# Power.net
KiCad netlist of a schematic drawn in Altium Designer
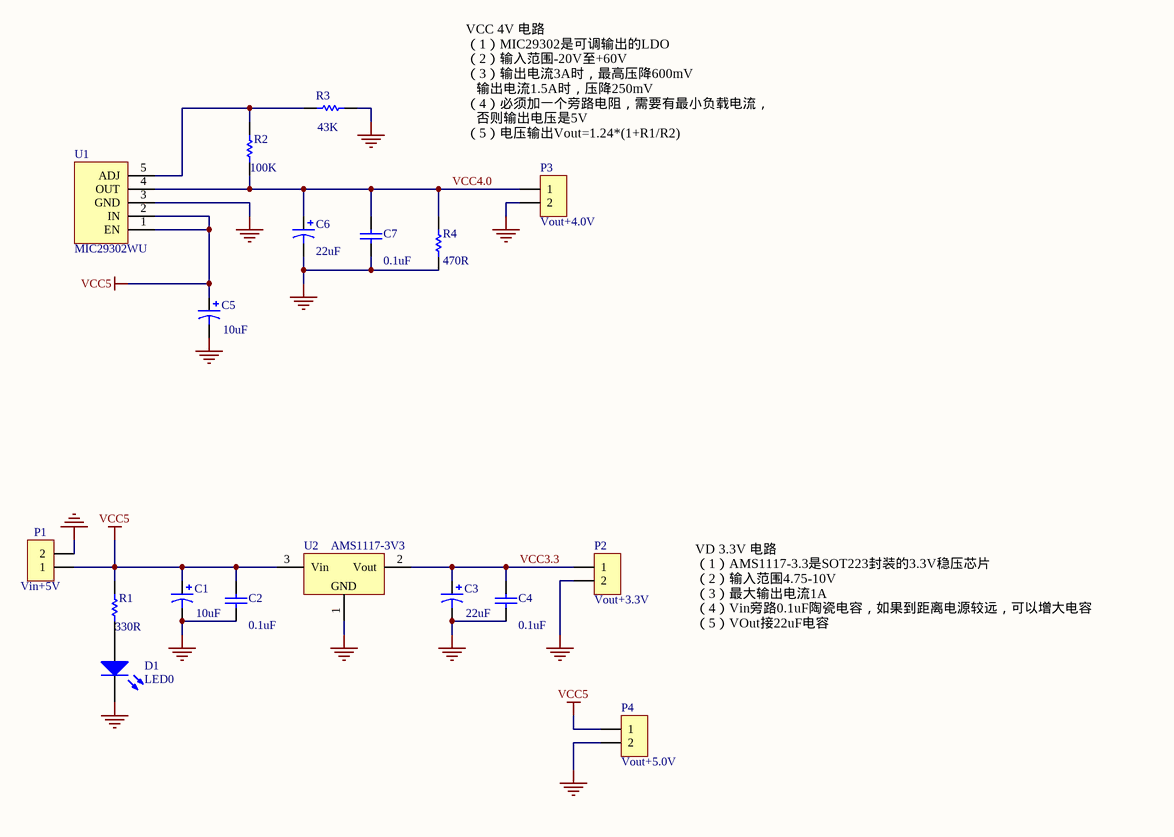
[diagram p0: Power.SchDoc]

(export (version "E")
  (design (tool "Eeschema 10.0.6"))
  (components
    (comp (ref "C1")
      (value "10uF")
      (footprint "CAP 2.0*5*11 - BK")
      (description "Polarized Capacitor (Radial)")
      (fields (field (name "Comment") "Cap Pol1") (field (name "PUBLISHER") "Altium Limited"))
      (libsource (lib "Miscellaneous Devices") (part "Cap Pol1"))
    )
    (comp (ref "C2")
      (value "0.1uF")
      (footprint "CC 2.2*5")
      (description "Capacitor")
      (fields (field (name "Comment") "Cap") (field (name "PUBLISHER") "Altium Limited"))
      (libsource (lib "Miscellaneous Devices") (part "Cap"))
    )
    (comp (ref "C3")
      (value "22uF")
      (footprint "CAP 2.0*5*11 - BK")
      (description "Polarized Capacitor (Radial)")
      (fields (field (name "Comment") "Cap Pol1") (field (name "PUBLISHER") "Altium Limited"))
      (libsource (lib "Miscellaneous Devices") (part "Cap Pol1"))
    )
    (comp (ref "C4")
      (value "0.1uF")
      (footprint "CC 2.2*5")
      (description "Capacitor")
      (fields (field (name "Comment") "Cap") (field (name "PUBLISHER") "Altium Limited"))
      (libsource (lib "Miscellaneous Devices") (part "Cap"))
    )
    (comp (ref "C5")
      (value "10uF")
      (footprint "CAP 2.0*5*11 - BK")
      (description "Polarized Capacitor (Radial)")
      (fields (field (name "Comment") "Cap Pol1") (field (name "PUBLISHER") "Altium Limited"))
      (libsource (lib "Miscellaneous Devices") (part "Cap Pol1"))
    )
    (comp (ref "C6")
      (value "22uF")
      (footprint "CAP 2.0*5*11 - BK")
      (description "Polarized Capacitor (Radial)")
      (fields (field (name "Comment") "Cap Pol1") (field (name "PUBLISHER") "Altium Limited"))
      (libsource (lib "Miscellaneous Devices") (part "Cap Pol1"))
    )
    (comp (ref "C7")
      (value "0.1uF")
      (footprint "CC 2.2*5")
      (description "Capacitor")
      (fields (field (name "Comment") "Cap") (field (name "PUBLISHER") "Altium Limited"))
      (libsource (lib "Miscellaneous Devices") (part "Cap"))
    )
    (comp (ref "D1")
      (value "LED0")
      (footprint "LED 3MM-R")
      (description "Typical INFRARED GaAs LED")
      (fields (field (name "PUBLISHER") "Altium Limited"))
      (libsource (lib "Miscellaneous Devices") (part "LED0"))
    )
    (comp (ref "P1")
      (value "Vin+5V")
      (footprint "XH2.54-2P")
      (description "2P接插件")
      (fields (field (name "版权归属") "源创客"))
      (libsource (lib "") (part "Header 2_1"))
    )
    (comp (ref "P2")
      (value "Vout+3.3V")
      (footprint "XH2.54-2P")
      (description "2P接插件")
      (fields (field (name "版权归属") "源创客"))
      (libsource (lib "接插件") (part "Header 2"))
    )
    (comp (ref "P3")
      (value "Vout+4.0V")
      (footprint "XH2.54-2P")
      (description "2P接插件")
      (fields (field (name "版权归属") "源创客"))
      (libsource (lib "接插件") (part "Header 2"))
    )
    (comp (ref "P4")
      (value "Vout+5.0V")
      (footprint "XH2.54-2P")
      (description "2P接插件")
      (fields (field (name "版权归属") "源创客"))
      (libsource (lib "接插件") (part "Header 2"))
    )
    (comp (ref "R1")
      (value "330R")
      (footprint "RS 1/4W")
      (description "Resistor")
      (fields (field (name "Comment") "Res1") (field (name "PUBLISHER") "Altium Limited"))
      (libsource (lib "Miscellaneous Devices") (part "Res1"))
    )
    (comp (ref "R2")
      (value "100K")
      (footprint "RS 1/4W")
      (description "Resistor")
      (fields (field (name "Comment") "Res1") (field (name "PUBLISHER") "Altium Limited"))
      (libsource (lib "Miscellaneous Devices") (part "Res1"))
    )
    (comp (ref "R3")
      (value "43K")
      (footprint "RS 1/4W")
      (description "Resistor")
      (fields (field (name "Comment") "Res1") (field (name "PUBLISHER") "Altium Limited"))
      (libsource (lib "Miscellaneous Devices") (part "Res1"))
    )
    (comp (ref "R4")
      (value "470R")
      (footprint "RS 1/4W")
      (description "Resistor")
      (fields (field (name "Comment") "Res1") (field (name "PUBLISHER") "Altium Limited"))
      (libsource (lib "Miscellaneous Devices") (part "Res1"))
    )
    (comp (ref "U1")
      (value "MIC29302WU")
      (footprint "TO263-5")
      (description "2A,  adjustable LDO")
      (libsource (lib "IC_电源") (part "MIC29302WU"))
    )
    (comp (ref "U2")
      (value "AMS1117-3V3")
      (footprint "SOT:SOT223_M")
      (description "三端稳压芯片")
      (fields (field (name "版权归属") "源创客"))
      (libsource (lib "IC芯片") (part "AMS1117"))
    )
  )
  (nets
    (net (code "1") (name "/VCC3.3") (class "Default")
      (node (ref "C3") (pin "1") (pinfunction "1_1") (pintype "passive"))
      (node (ref "C4") (pin "2") (pinfunction "2_2") (pintype "passive"))
      (node (ref "P2") (pin "1") (pinfunction "1_1") (pintype "passive"))
      (node (ref "U2") (pin "2") (pinfunction "Vout_2") (pintype "passive"))
    )
    (net (code "2") (name "/VCC4.0") (class "Default")
      (node (ref "C6") (pin "1") (pinfunction "1_1") (pintype "passive"))
      (node (ref "C7") (pin "2") (pinfunction "2_2") (pintype "passive"))
      (node (ref "P3") (pin "1") (pinfunction "1_1") (pintype "passive"))
      (node (ref "R2") (pin "1") (pinfunction "1_1") (pintype "passive"))
      (node (ref "R4") (pin "2") (pinfunction "2_2") (pintype "passive"))
      (node (ref "U1") (pin "4") (pinfunction "OUT_4") (pintype "passive"))
    )
    (net (code "3") (name "GND") (class "Default")
      (node (ref "C1") (pin "2") (pinfunction "2_2") (pintype "passive"))
      (node (ref "C2") (pin "1") (pinfunction "1_1") (pintype "passive"))
      (node (ref "C3") (pin "2") (pinfunction "2_2") (pintype "passive"))
      (node (ref "C4") (pin "1") (pinfunction "1_1") (pintype "passive"))
      (node (ref "C5") (pin "2") (pinfunction "2_2") (pintype "passive"))
      (node (ref "C6") (pin "2") (pinfunction "2_2") (pintype "passive"))
      (node (ref "C7") (pin "1") (pinfunction "1_1") (pintype "passive"))
      (node (ref "D1") (pin "2") (pinfunction "K_2") (pintype "passive"))
      (node (ref "P1") (pin "2") (pinfunction "2_2") (pintype "passive"))
      (node (ref "P2") (pin "2") (pinfunction "2_2") (pintype "passive"))
      (node (ref "P3") (pin "2") (pinfunction "2_2") (pintype "passive"))
      (node (ref "P4") (pin "2") (pinfunction "2_2") (pintype "passive"))
      (node (ref "R3") (pin "1") (pinfunction "1_1") (pintype "passive"))
      (node (ref "R4") (pin "1") (pinfunction "1_1") (pintype "passive"))
      (node (ref "U1") (pin "3") (pinfunction "GND_3") (pintype "passive"))
      (node (ref "U2") (pin "1") (pinfunction "GND_1") (pintype "passive"))
    )
    (net (code "4") (name "Net-(D1-A)") (class "Default")
      (node (ref "D1") (pin "1") (pinfunction "A_1") (pintype "passive"))
      (node (ref "R1") (pin "1") (pinfunction "1_1") (pintype "passive"))
    )
    (net (code "5") (name "Net-(U1-ADJ)") (class "Default")
      (node (ref "R2") (pin "2") (pinfunction "2_2") (pintype "passive"))
      (node (ref "R3") (pin "2") (pinfunction "2_2") (pintype "passive"))
      (node (ref "U1") (pin "5") (pinfunction "ADJ_5") (pintype "passive"))
    )
    (net (code "6") (name "VCC5") (class "Default")
      (node (ref "C1") (pin "1") (pinfunction "1_1") (pintype "passive"))
      (node (ref "C2") (pin "2") (pinfunction "2_2") (pintype "passive"))
      (node (ref "C5") (pin "1") (pinfunction "1_1") (pintype "passive"))
      (node (ref "P1") (pin "1") (pinfunction "1_1") (pintype "passive"))
      (node (ref "P4") (pin "1") (pinfunction "1_1") (pintype "passive"))
      (node (ref "R1") (pin "2") (pinfunction "2_2") (pintype "passive"))
      (node (ref "U1") (pin "1") (pinfunction "EN_1") (pintype "passive"))
      (node (ref "U1") (pin "2") (pinfunction "IN_2") (pintype "passive"))
      (node (ref "U2") (pin "3") (pinfunction "Vin_3") (pintype "passive"))
    )
  )
)
